# USB-IRIS-W1_POWER_COMM.net
KiCad netlist of a schematic drawn in Altium Designer
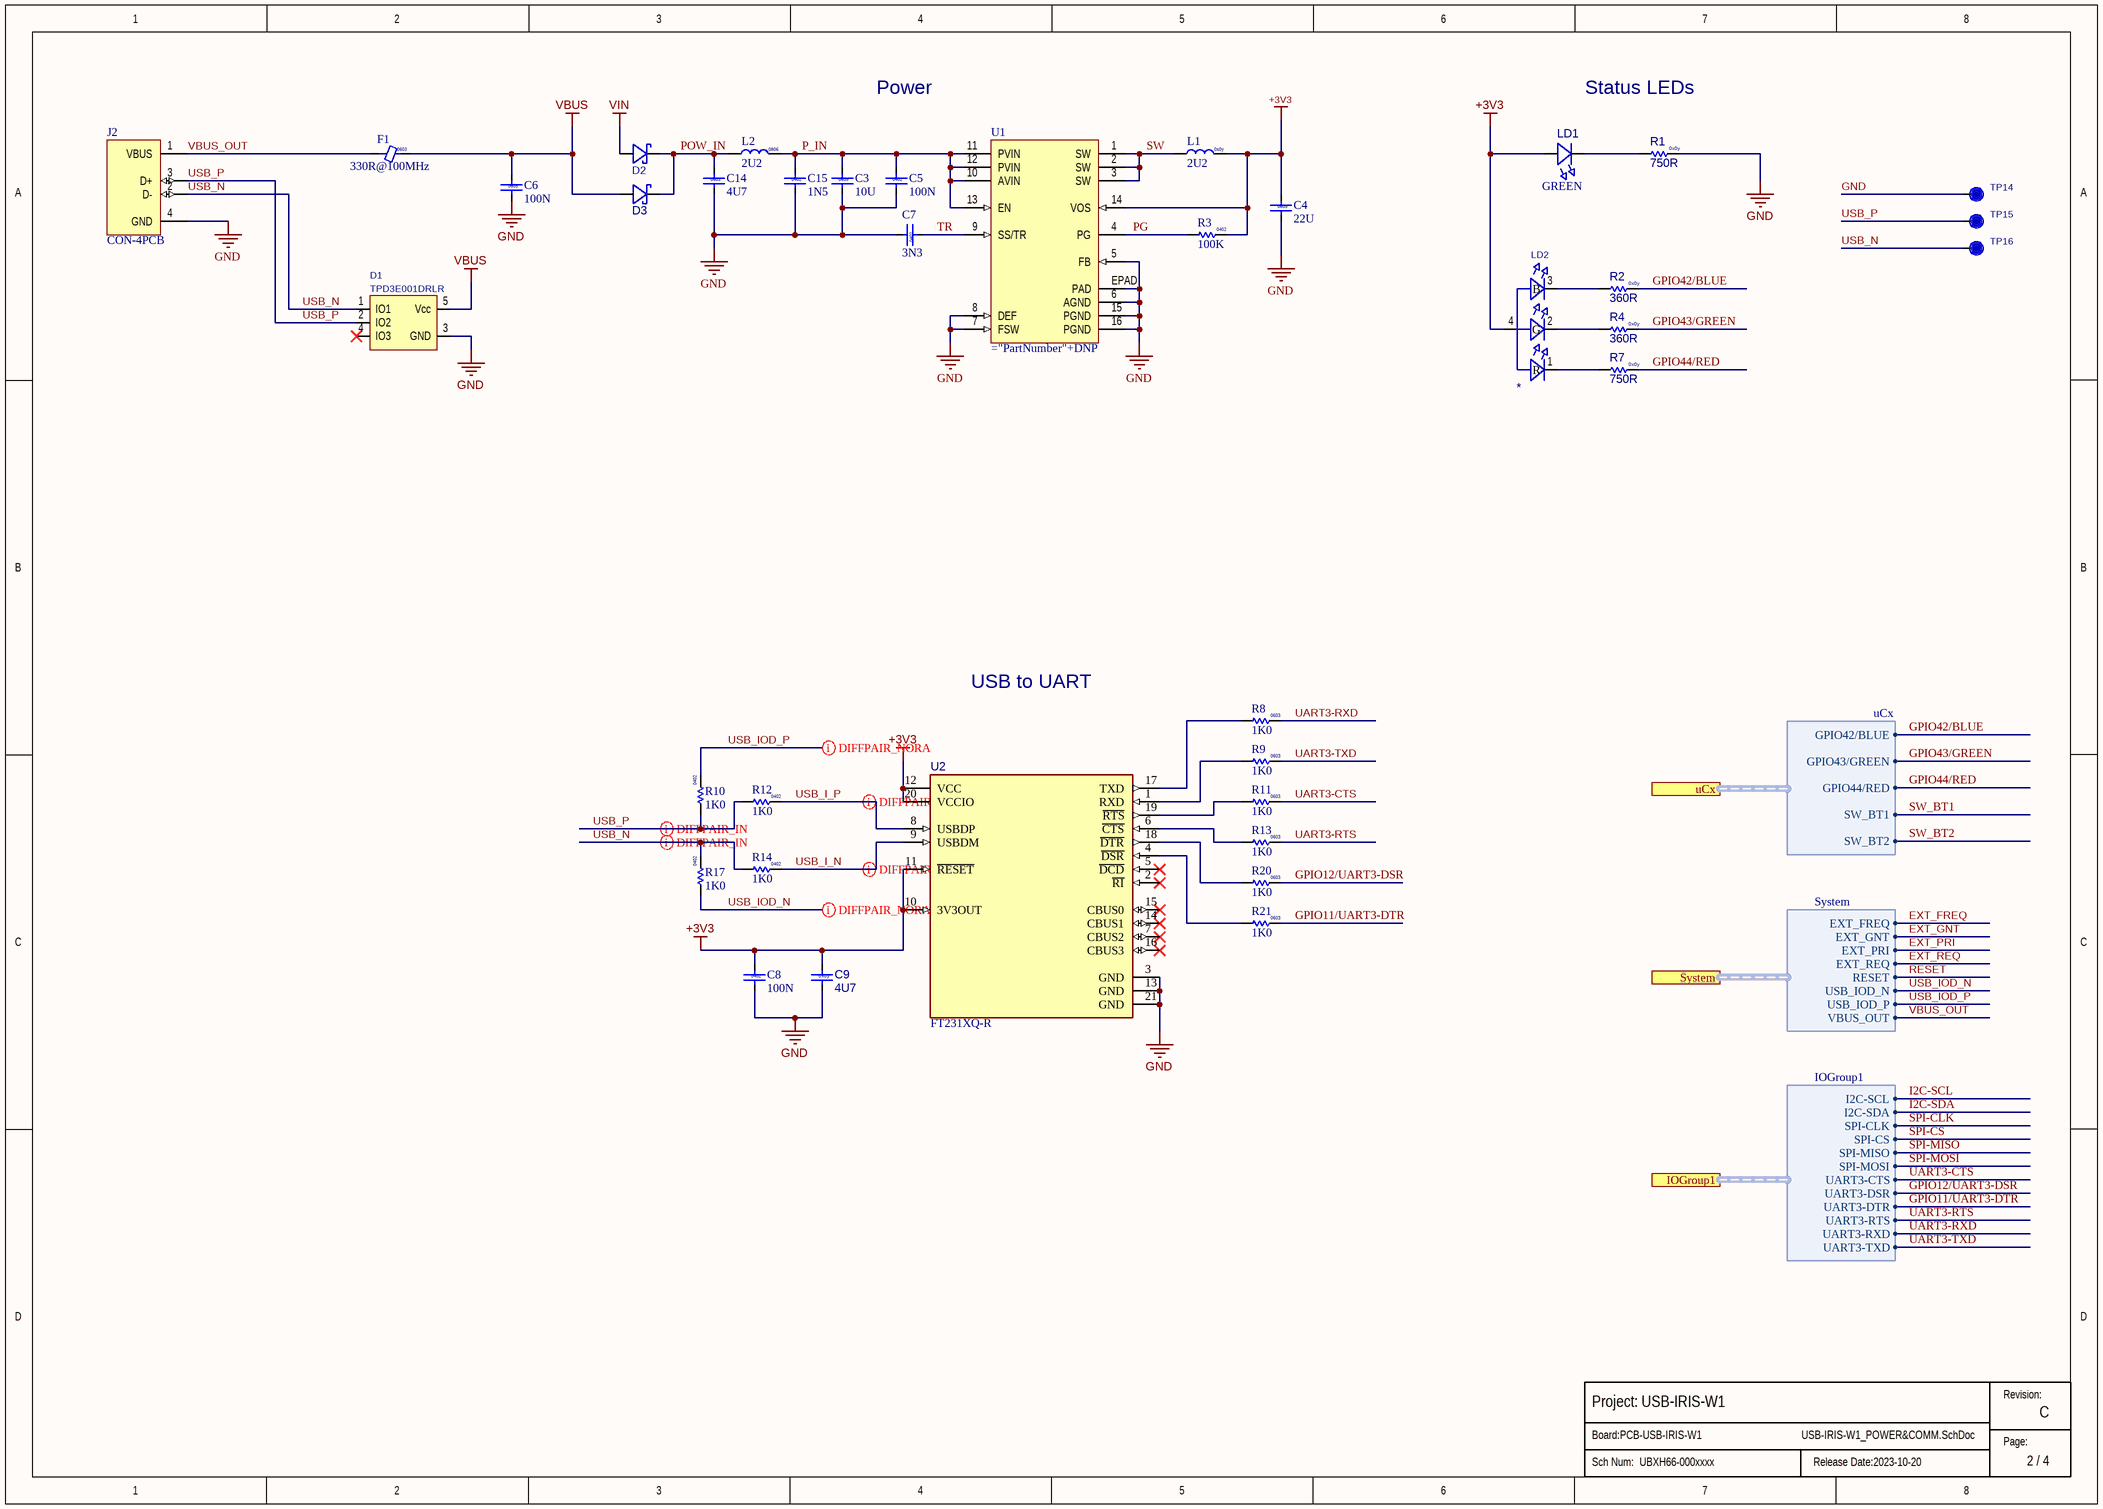
[diagram p0: USB-IRIS-W1_POWER&COMM.SchDoc]

(export (version "E")
  (design (tool "Eeschema 10.0.6"))
  (components
    (comp (ref "C3")
      (value "10U")
      (footprint "Cap 0805 HD")
      (description "CAP CER X5R 0805 10U 10% 25V")
      (fields
        (field (name "SIZE") "0805")
        (field (name "PART NUMBER") "UBXH01-0000261")
        (field (name "TOLERANCE") "10%")
        (field (name "EDITOR") "erian.bezhani")
        (field (name "RELEASED BY") "alex.claville")
      )
      (libsource (lib "UBX_Parts_DB_Lib") (part "Cap Chip"))
    )
    (comp (ref "C4")
      (value "22U")
      (footprint "Cap 0805 HD")
      (description "CAP CER X5R 0805 22U 20% 25V")
      (fields
        (field (name "SIZE") "0805")
        (field (name "PART NUMBER") "UBXH01-0000414")
        (field (name "TOLERANCE") "20%")
        (field (name "EDITOR") "jaakko.jussila")
      )
      (libsource (lib "UBX_Parts_DB_Lib") (part "Cap Chip"))
    )
    (comp (ref "C5")
      (value "100N")
      (footprint "Cap 0402 HD")
      (description "CAP CER X5R 0402 100N 10% 10V")
      (fields
        (field (name "SIZE") "0402")
        (field (name "PART NUMBER") "UBXH01-2021002")
        (field (name "TOLERANCE") "10%")
        (field (name "EDITOR") "roland.rust")
        (field (name "RELEASED BY") "roland.rust")
      )
      (libsource (lib "UBX_Parts_DB_Lib") (part "Cap Chip"))
    )
    (comp (ref "C6")
      (value "100N")
      (footprint "CAP_0603_1750Lx950Wx850H_600x1000Pad_900G_FLX")
      (description "CAP CER X7R 0603 100N 10% 50V")
      (fields
        (field (name "SIZE") "0603")
        (field (name "PART NUMBER") "UBXH01-2022001")
        (field (name "TOLERANCE") "10%")
        (field (name "EDITOR") "andreas.thiel")
        (field (name "RELEASED BY") "johann.furrer")
      )
      (libsource (lib "UBX_Parts_DB_Lib") (part "Cap Chip"))
    )
    (comp (ref "C7")
      (value "3N3")
      (footprint "CAP 0402")
      (description "CAP CER X7R 0402 3N3 10% 16V")
      (fields
        (field (name "SIZE") "0402")
        (field (name "PART NUMBER") "UBXH01-0023019")
        (field (name "TOLERANCE") "10%")
        (field (name "EDITOR") "dario.antonaz")
        (field (name "RELEASED BY") "pierpaolo.arban")
      )
      (libsource (lib "UBX_Parts_DB_Lib") (part "Cap Chip"))
    )
    (comp (ref "C8")
      (value "100N")
      (footprint "Cap 0402 HD")
      (description "CAP CER X5R 0402 100N 10% 10V")
      (fields
        (field (name "SIZE") "0402")
        (field (name "PART NUMBER") "UBXH01-2021002")
        (field (name "TOLERANCE") "10%")
        (field (name "EDITOR") "roland.rust")
        (field (name "RELEASED BY") "roland.rust")
      )
      (libsource (lib "UBX_Parts_DB_Lib") (part "Cap Chip"))
    )
    (comp (ref "C9")
      (value "4U7")
      (footprint "Cap 0402 HD")
      (description "CAP CER X5R 0402")
      (fields
        (field (name "SIZE") "0x0y")
        (field (name "PART NUMBER") "UBXH01-0000243")
        (field (name "TOLERANCE") "20%")
        (field (name "EDITOR") "dario.antonaz")
        (field (name "RELEASED BY") "pasquale.scorca")
      )
      (libsource (lib "UBX_Parts_DB_Lib") (part "Cap Chip"))
    )
    (comp (ref "C14")
      (value "4U7")
      (footprint "CAP_0603_1800Lx1000Wx1000H_600x1000Pad_900G_FLX")
      (description "CAP CER X5R 0603 4U7 20% 10V")
      (fields
        (field (name "SIZE") "0603")
        (field (name "PART NUMBER") "UBXH01-0000247")
        (field (name "TOLERANCE") "20%")
        (field (name "EDITOR") "dario.antonaz")
        (field (name "RELEASED BY") "martin.grasse")
      )
      (libsource (lib "UBX_Parts_DB_Lib") (part "Cap Chip"))
    )
    (comp (ref "C15")
      (value "1N5")
      (footprint "CAP 0402")
      (description "CAP CER X7R 0402 1N5 10% 50V")
      (fields
        (field (name "SIZE") "0402")
        (field (name "PART NUMBER") "UBXH01-0000211")
        (field (name "TOLERANCE") "10%")
        (field (name "EDITOR") "domenico.volpe")
        (field (name "RELEASED BY") "massimo.vlacci")
      )
      (libsource (lib "UBX_Parts_DB_Lib") (part "Cap Chip"))
    )
    (comp (ref "D1")
      (value "110-00018")
      (footprint "SOT-553")
      (description "LOW-CAPACITANCE 3-CHANNEL ESD-PROTECTION ARRAY")
      (fields
        (field (name "MANUFACTURER P/N") "TPD3E001DRLR")
        (field (name "MANUFACTURER") "Texas Instruments")
        (field (name "VOLTAGE") "5V")
      )
      (libsource (lib "Arena_Parts_DB_Lib") (part "TPD3E001"))
    )
    (comp (ref "D2")
      (value "110-00005")
      (footprint "SOD-123F_U")
      (description "Diode, Schottky, 20V 1A SOD-123F, 340mV Vf @ 1A\nMBR120VLSFT3G")
      (fields (field (name "VOLTAGE") "20V"))
      (libsource (lib "Arena_Parts_DB_Lib") (part "Diode_Schottky"))
    )
    (comp (ref "D3")
      (value "110-00005")
      (footprint "SOD-123F_U")
      (description "Diode, Schottky, 20V 1A SOD-123F, 340mV Vf @ 1A\nMBR120VLSFT3G")
      (fields (field (name "VOLTAGE") "20V"))
      (libsource (lib "Arena_Parts_DB_Lib") (part "Diode_Schottky"))
    )
    (comp (ref "F1")
      (value "330R@100MHz")
      (footprint "IND 0603 HD:IND 0603 HD")
      (description "FERRITE BEAD MURATA BLM18KG 0603 330R@100MHz")
      (fields (field (name "MANUFACTURER") "Murata Electronics") (field (name "SIZE") "0603"))
      (libsource (lib "Schlib1") (part "FB sm"))
    )
    (comp (ref "J2")
      (value "CON-4PCB")
      (footprint "USB-A-PCB")
      (description "CONN USB PLUG A TYPE PCB FOOTPRINT")
      (fields (field (name "PART NUMBER") "UBXH04-0000711") (field (name "EDITOR") "aneeb.sohail"))
      (libsource (lib "UBX_Parts_DB_Lib") (part "CON-4PCB"))
    )
    (comp (ref "L1")
      (value "2U2")
      (footprint "Ind_4mmx4mm")
      (description "SHIELDED POWER INDUCTOR XFL4020 2U2 20% 3.1A")
      (fields
        (field (name "SIZE") "0x0y")
        (field (name "PART NUMBER") "UBXH09-0000176")
        (field (name "TOLERANCE") "20%")
        (field (name "EDITOR") "roland.rust")
        (field (name "RELEASED BY") "olof.viklund")
      )
      (libsource (lib "UBX_Parts_DB_Lib") (part "Ind sm"))
    )
    (comp (ref "L2")
      (value "2U2")
      (footprint "IND 0806")
      (description "IND MURATA LQM2MP 0806 2U2 30% 1.2A")
      (fields
        (field (name "SIZE") "0806")
        (field (name "PART NUMBER") "UBXH09-0000025")
        (field (name "TOLERANCE") "30%")
        (field (name "EDITOR") "martin.pilik")
        (field (name "RELEASED BY") "fabrice.bret-dibat")
      )
      (libsource (lib "UBX_Parts_DB_Lib") (part "Ind sm"))
    )
    (comp (ref "LD1")
      (value "GREEN")
      (footprint "LED-0603")
      (description "LED CHIP 0603 LOW CURRENT OSRAM 0.002A")
      (fields
        (field (name "PART NUMBER") "UBXH11-0000018")
        (field (name "MANUFACTURER") "Osram")
        (field (name "EDITOR") "johann.furrer")
        (field (name "RELEASED BY") "martin.grasse")
      )
      (libsource (lib "UBX_Parts_DB_Lib") (part "LED_BASE"))
    )
    (comp (ref "LD2")
      (value "115-00026")
      (footprint "LED_1616")
      (description "LED RGB SMT 0606")
      (fields (field (name "COLOR") "*") (field (name "VOLTAGE") "None"))
      (libsource (lib "Arena_Parts_DB_Lib") (part "LED_RGB_CA_4"))
    )
    (comp (ref "R1")
      (value "750R")
      (footprint "RES 0402 HD")
      (description "RES THICK FILM CHIP 0402")
      (fields
        (field (name "SIZE") "0x0y")
        (field (name "PART NUMBER") "UBXH18-0008046")
        (field (name "TOLERANCE") "5%")
        (field (name "EDITOR") "jaka.bevk")
        (field (name "RELEASED BY") "erian.bezhani")
      )
      (libsource (lib "UBX_Parts_DB_Lib") (part "Res sm"))
    )
    (comp (ref "R2")
      (value "360R")
      (footprint "RES 0402 HD")
      (description "RES THICK FILM CHIP 0402")
      (fields
        (field (name "SIZE") "0x0y")
        (field (name "PART NUMBER") "UBXH18-0000216")
        (field (name "TOLERANCE") "1%")
        (field (name "EDITOR") "michael.hein")
        (field (name "RELEASED BY") "vasyl.dykyy")
      )
      (libsource (lib "UBX_Parts_DB_Lib") (part "Res sm"))
    )
    (comp (ref "R3")
      (value "100K")
      (footprint "RES 0402 HD")
      (description "RES THICK FILM CHIP 0402 100K 1% 63mW")
      (fields
        (field (name "SIZE") "0402")
        (field (name "PART NUMBER") "UBXH18-0000005")
        (field (name "TOLERANCE") "1%")
        (field (name "EDITOR") "dario.antonaz")
        (field (name "RELEASED BY") "sandro.sestan")
      )
      (libsource (lib "UBX_Parts_DB_Lib") (part "Res sm"))
    )
    (comp (ref "R4")
      (value "360R")
      (footprint "RES 0402 HD")
      (description "RES THICK FILM CHIP 0402")
      (fields
        (field (name "SIZE") "0x0y")
        (field (name "PART NUMBER") "UBXH18-0000216")
        (field (name "TOLERANCE") "1%")
        (field (name "EDITOR") "michael.hein")
        (field (name "RELEASED BY") "vasyl.dykyy")
      )
      (libsource (lib "UBX_Parts_DB_Lib") (part "Res sm"))
    )
    (comp (ref "R7")
      (value "750R")
      (footprint "RES 0402 HD")
      (description "RES THICK FILM CHIP 0402")
      (fields
        (field (name "SIZE") "0x0y")
        (field (name "PART NUMBER") "UBXH18-0008046")
        (field (name "TOLERANCE") "5%")
        (field (name "EDITOR") "jaka.bevk")
        (field (name "RELEASED BY") "erian.bezhani")
      )
      (libsource (lib "UBX_Parts_DB_Lib") (part "Res sm"))
    )
    (comp (ref "R8")
      (value "1K0")
      (footprint "RES 0603 HD")
      (description "RES THICK FILM CHIP 0603 1K0 5% 100mW")
      (fields
        (field (name "SIZE") "0603")
        (field (name "PART NUMBER") "UBXH18-0007073")
        (field (name "TOLERANCE") "5%")
        (field (name "EDITOR") "roland.rust")
        (field (name "RELEASED BY") "roland.rust")
      )
      (libsource (lib "UBX_Parts_DB_Lib") (part "Res sm"))
    )
    (comp (ref "R9")
      (value "1K0")
      (footprint "RES 0603 HD")
      (description "RES THICK FILM CHIP 0603 1K0 5% 100mW")
      (fields
        (field (name "SIZE") "0603")
        (field (name "PART NUMBER") "UBXH18-0007073")
        (field (name "TOLERANCE") "5%")
        (field (name "EDITOR") "roland.rust")
        (field (name "RELEASED BY") "roland.rust")
      )
      (libsource (lib "UBX_Parts_DB_Lib") (part "Res sm"))
    )
    (comp (ref "R10")
      (value "1K0")
      (footprint "RES 0402 HD")
      (description "RES THICK FILM CHIP 0402 1K0 5% 100mW")
      (fields
        (field (name "SIZE") "0402")
        (field (name "PART NUMBER") "UBXH18-0008049")
        (field (name "TOLERANCE") "5%")
        (field (name "EDITOR") "roland.rust")
        (field (name "RELEASED BY") "roland.rust")
      )
      (libsource (lib "UBX_Parts_DB_Lib") (part "Res sm"))
    )
    (comp (ref "R11")
      (value "1K0")
      (footprint "RES 0603 HD")
      (description "RES THICK FILM CHIP 0603 1K0 5% 100mW")
      (fields
        (field (name "SIZE") "0603")
        (field (name "PART NUMBER") "UBXH18-0007073")
        (field (name "TOLERANCE") "5%")
        (field (name "EDITOR") "roland.rust")
        (field (name "RELEASED BY") "roland.rust")
      )
      (libsource (lib "UBX_Parts_DB_Lib") (part "Res sm"))
    )
    (comp (ref "R12")
      (value "1K0")
      (footprint "RES 0402 HD")
      (description "RES THICK FILM CHIP 0402 1K0 5% 100mW")
      (fields
        (field (name "SIZE") "0402")
        (field (name "PART NUMBER") "UBXH18-0008049")
        (field (name "TOLERANCE") "5%")
        (field (name "EDITOR") "roland.rust")
        (field (name "RELEASED BY") "roland.rust")
      )
      (libsource (lib "UBX_Parts_DB_Lib") (part "Res sm"))
    )
    (comp (ref "R13")
      (value "1K0")
      (footprint "RES 0603 HD")
      (description "RES THICK FILM CHIP 0603 1K0 5% 100mW")
      (fields
        (field (name "SIZE") "0603")
        (field (name "PART NUMBER") "UBXH18-0007073")
        (field (name "TOLERANCE") "5%")
        (field (name "EDITOR") "roland.rust")
        (field (name "RELEASED BY") "roland.rust")
      )
      (libsource (lib "UBX_Parts_DB_Lib") (part "Res sm"))
    )
    (comp (ref "R14")
      (value "1K0")
      (footprint "RES 0402 HD")
      (description "RES THICK FILM CHIP 0402 1K0 5% 100mW")
      (fields
        (field (name "SIZE") "0402")
        (field (name "PART NUMBER") "UBXH18-0008049")
        (field (name "TOLERANCE") "5%")
        (field (name "EDITOR") "roland.rust")
        (field (name "RELEASED BY") "roland.rust")
      )
      (libsource (lib "UBX_Parts_DB_Lib") (part "Res sm"))
    )
    (comp (ref "R17")
      (value "1K0")
      (footprint "RES 0402 HD")
      (description "RES THICK FILM CHIP 0402 1K0 5% 100mW")
      (fields
        (field (name "SIZE") "0402")
        (field (name "PART NUMBER") "UBXH18-0008049")
        (field (name "TOLERANCE") "5%")
        (field (name "EDITOR") "roland.rust")
        (field (name "RELEASED BY") "roland.rust")
      )
      (libsource (lib "UBX_Parts_DB_Lib") (part "Res sm"))
    )
    (comp (ref "R20")
      (value "1K0")
      (footprint "RES 0603 HD")
      (description "RES THICK FILM CHIP 0603 1K0 5% 100mW")
      (fields
        (field (name "SIZE") "0603")
        (field (name "PART NUMBER") "UBXH18-0007073")
        (field (name "TOLERANCE") "5%")
        (field (name "EDITOR") "roland.rust")
        (field (name "RELEASED BY") "roland.rust")
      )
      (libsource (lib "UBX_Parts_DB_Lib") (part "Res sm"))
    )
    (comp (ref "R21")
      (value "1K0")
      (footprint "RES 0603 HD")
      (description "RES THICK FILM CHIP 0603 1K0 5% 100mW")
      (fields
        (field (name "SIZE") "0603")
        (field (name "PART NUMBER") "UBXH18-0007073")
        (field (name "TOLERANCE") "5%")
        (field (name "EDITOR") "roland.rust")
        (field (name "RELEASED BY") "roland.rust")
      )
      (libsource (lib "UBX_Parts_DB_Lib") (part "Res sm"))
    )
    (comp (ref "TP14")
      (value "TP")
      (footprint "TP10R")
      (description "Testpoint, Round 1.0mm Dia")
      (fields
        (field (name "PART NUMBER") "TP10R")
        (field (name "ADDED BY") "Jeremy D")
        (field (name "CHECKED BY") "Paul B")
      )
      (libsource (lib "LEGACY_Rigado_AltiumLib") (part "TP_R"))
    )
    (comp (ref "TP15")
      (value "TP")
      (footprint "TP10R")
      (description "Testpoint, Round 1.0mm Dia")
      (fields
        (field (name "PART NUMBER") "TP10R")
        (field (name "ADDED BY") "Jeremy D")
        (field (name "CHECKED BY") "Paul B")
      )
      (libsource (lib "LEGACY_Rigado_AltiumLib") (part "TP_R"))
    )
    (comp (ref "TP16")
      (value "TP")
      (footprint "TP10R")
      (description "Testpoint, Round 1.0mm Dia")
      (fields
        (field (name "PART NUMBER") "TP10R")
        (field (name "ADDED BY") "Jeremy D")
        (field (name "CHECKED BY") "Paul B")
      )
      (libsource (lib "LEGACY_Rigado_AltiumLib") (part "TP_R"))
    )
    (comp (ref "U1")
      (value "TPS62132RGTR")
      (footprint "QFN0.5P3x3-16Pin_W-Pad")
      (description "STEP DOWN DC-DC CONVERTER 3-17V 3A TPS62132 3V3")
      (fields
        (field (name "MANUFACTURER") "Texas Instruments")
        (field (name "PART NUMBER") "UBXH12-0000160")
        (field (name "EDITOR") "andre.pick")
        (field (name "RELEASED BY") "alvaro.nussbaum")
      )
      (libsource (lib "Schlib1") (part "UBXH12-0000160"))
    )
    (comp (ref "U2")
      (value "FT231XQ-R")
      (footprint "QFN_5x5_FT231XQ")
      (description "FTDI USB TO SERIAL FULL UART INTERFACE QFN20")
      (fields
        (field (name "PART NUMBER") "UBXH10-0000054")
        (field (name "MANUFACTURER") "FTDI Future Technology Devices International")
        (field (name "EDITOR") "adam.johansson")
      )
      (libsource (lib "UBX_Parts_DB_Lib") (part "FT231XQ-R"))
    )
  )
  (nets
    (net (code "4") (name "+3V3") (class "Default")
      (node (ref "C4") (pin "1") (pinfunction "1_1") (pintype "passive"))
      (node (ref "C8") (pin "1") (pinfunction "1_1") (pintype "passive"))
      (node (ref "C9") (pin "1") (pinfunction "1_1") (pintype "passive"))
      (node (ref "L1") (pin "2") (pinfunction "2_2") (pintype "passive"))
      (node (ref "LD1") (pin "2") (pinfunction "A_2") (pintype "passive"))
      (node (ref "LD2") (pin "4") (pinfunction "A_4") (pintype "passive"))
      (node (ref "R3") (pin "2") (pinfunction "2_2") (pintype "passive"))
      (node (ref "U1") (pin "14") (pinfunction "VOS_14") (pintype "input"))
      (node (ref "U2") (pin "10") (pinfunction "3V3OUT_10") (pintype "input"))
      (node (ref "U2") (pin "11") (pinfunction "~{RESET}_11") (pintype "input"))
      (node (ref "U2") (pin "12") (pinfunction "VCC_12") (pintype "power_in"))
      (node (ref "U2") (pin "20") (pinfunction "VCCIO_20") (pintype "power_in"))
    )
    (net (code "9") (name "/GPIO11{slash}UART3-DTR") (class "Default")
      (node (ref "R21") (pin "2") (pinfunction "2_2") (pintype "passive"))
    )
    (net (code "10") (name "/GPIO12{slash}UART3-DSR") (class "Default")
      (node (ref "R20") (pin "2") (pinfunction "2_2") (pintype "passive"))
    )
    (net (code "11") (name "/GPIO42{slash}BLUE") (class "Default")
      (node (ref "R2") (pin "2") (pinfunction "2_2") (pintype "passive"))
    )
    (net (code "12") (name "/GPIO43{slash}GREEN") (class "Default")
      (node (ref "R4") (pin "2") (pinfunction "2_2") (pintype "passive"))
    )
    (net (code "13") (name "/GPIO44{slash}RED") (class "Default")
      (node (ref "R7") (pin "2") (pinfunction "2_2") (pintype "passive"))
    )
    (net (code "16") (name "/PG") (class "Default")
      (node (ref "R3") (pin "1") (pinfunction "1_1") (pintype "passive"))
      (node (ref "U1") (pin "4") (pinfunction "PG_4") (pintype "tri_state"))
    )
    (net (code "17") (name "/POW_IN") (class "Default")
      (node (ref "C14") (pin "1") (pinfunction "1_1") (pintype "passive"))
      (node (ref "D2") (pin "C") (pinfunction "Cathode_C") (pintype "passive"))
      (node (ref "D3") (pin "C") (pinfunction "Cathode_C") (pintype "passive"))
      (node (ref "L2") (pin "1") (pinfunction "1_1") (pintype "passive"))
    )
    (net (code "18") (name "/P_IN") (class "Default")
      (node (ref "C15") (pin "1") (pinfunction "1_1") (pintype "passive"))
      (node (ref "C3") (pin "1") (pinfunction "1_1") (pintype "passive"))
      (node (ref "C5") (pin "1") (pinfunction "1_1") (pintype "passive"))
      (node (ref "L2") (pin "2") (pinfunction "2_2") (pintype "passive"))
      (node (ref "U1") (pin "10") (pinfunction "AVIN_10") (pintype "power_in"))
      (node (ref "U1") (pin "11") (pinfunction "PVIN_11") (pintype "power_in"))
      (node (ref "U1") (pin "12") (pinfunction "PVIN_12") (pintype "power_in"))
      (node (ref "U1") (pin "13") (pinfunction "EN_13") (pintype "input"))
    )
    (net (code "24") (name "/SW") (class "Default")
      (node (ref "L1") (pin "1") (pinfunction "1_1") (pintype "passive"))
      (node (ref "U1") (pin "1") (pinfunction "SW_1") (pintype "power_in"))
      (node (ref "U1") (pin "2") (pinfunction "SW_2") (pintype "power_in"))
      (node (ref "U1") (pin "3") (pinfunction "SW_3") (pintype "power_in"))
    )
    (net (code "27") (name "/TR") (class "Default")
      (node (ref "C7") (pin "1") (pinfunction "1_1") (pintype "passive"))
      (node (ref "U1") (pin "9") (pinfunction "SS/TR_9") (pintype "input"))
    )
    (net (code "28") (name "/UART3-CTS") (class "Default")
      (node (ref "R11") (pin "2") (pinfunction "2_2") (pintype "passive"))
    )
    (net (code "29") (name "/UART3-RTS") (class "Default")
      (node (ref "R13") (pin "2") (pinfunction "2_2") (pintype "passive"))
    )
    (net (code "30") (name "/UART3-RXD") (class "Default")
      (node (ref "R8") (pin "2") (pinfunction "2_2") (pintype "passive"))
    )
    (net (code "31") (name "/UART3-TXD") (class "Default")
      (node (ref "R9") (pin "2") (pinfunction "2_2") (pintype "passive"))
    )
    (net (code "32") (name "/USB_IOD_N") (class "Default")
      (node (ref "R17") (pin "1") (pinfunction "1_1") (pintype "passive"))
    )
    (net (code "33") (name "/USB_IOD_P") (class "Default")
      (node (ref "R10") (pin "2") (pinfunction "2_2") (pintype "passive"))
    )
    (net (code "34") (name "/USB_I_N") (class "Default")
      (node (ref "R14") (pin "2") (pinfunction "2_2") (pintype "passive"))
      (node (ref "U2") (pin "9") (pinfunction "USBDM_9") (pintype "input"))
    )
    (net (code "35") (name "/USB_I_P") (class "Default")
      (node (ref "R12") (pin "2") (pinfunction "2_2") (pintype "passive"))
      (node (ref "U2") (pin "8") (pinfunction "USBDP_8") (pintype "input"))
    )
    (net (code "36") (name "/USB_N") (class "Default")
      (node (ref "D1") (pin "1") (pinfunction "IO1_1") (pintype "passive"))
      (node (ref "J2") (pin "2") (pinfunction "D-_2") (pintype "bidirectional"))
      (node (ref "R14") (pin "1") (pinfunction "1_1") (pintype "passive"))
      (node (ref "R17") (pin "2") (pinfunction "2_2") (pintype "passive"))
      (node (ref "TP16") (pin "1") (pintype "passive"))
    )
    (net (code "37") (name "/USB_P") (class "Default")
      (node (ref "D1") (pin "2") (pinfunction "IO2_2") (pintype "passive"))
      (node (ref "J2") (pin "3") (pinfunction "D+_3") (pintype "bidirectional"))
      (node (ref "R10") (pin "1") (pinfunction "1_1") (pintype "passive"))
      (node (ref "R12") (pin "1") (pinfunction "1_1") (pintype "passive"))
      (node (ref "TP15") (pin "1") (pintype "passive"))
    )
    (net (code "38") (name "/VBUS_OUT") (class "Default")
      (node (ref "F1") (pin "1") (pinfunction "1_1") (pintype "passive"))
      (node (ref "J2") (pin "1") (pinfunction "VBUS_1") (pintype "power_in"))
    )
    (net (code "42") (name "GND") (class "Default")
      (node (ref "C14") (pin "2") (pinfunction "2_2") (pintype "passive"))
      (node (ref "C15") (pin "2") (pinfunction "2_2") (pintype "passive"))
      (node (ref "C3") (pin "2") (pinfunction "2_2") (pintype "passive"))
      (node (ref "C4") (pin "2") (pinfunction "2_2") (pintype "passive"))
      (node (ref "C5") (pin "2") (pinfunction "2_2") (pintype "passive"))
      (node (ref "C6") (pin "2") (pinfunction "2_2") (pintype "passive"))
      (node (ref "C7") (pin "2") (pinfunction "2_2") (pintype "passive"))
      (node (ref "C8") (pin "2") (pinfunction "2_2") (pintype "passive"))
      (node (ref "C9") (pin "2") (pinfunction "2_2") (pintype "passive"))
      (node (ref "D1") (pin "3") (pinfunction "GND_3") (pintype "power_in"))
      (node (ref "J2") (pin "4") (pinfunction "GND_4") (pintype "power_in"))
      (node (ref "R1") (pin "2") (pinfunction "2_2") (pintype "passive"))
      (node (ref "TP14") (pin "1") (pintype "passive"))
      (node (ref "U1") (pin "15") (pinfunction "PGND_15") (pintype "power_in"))
      (node (ref "U1") (pin "16") (pinfunction "PGND_16") (pintype "power_in"))
      (node (ref "U1") (pin "5") (pinfunction "FB_5") (pintype "input"))
      (node (ref "U1") (pin "6") (pinfunction "AGND_6") (pintype "power_in"))
      (node (ref "U1") (pin "7") (pinfunction "FSW_7") (pintype "input"))
      (node (ref "U1") (pin "8") (pinfunction "DEF_8") (pintype "input"))
      (node (ref "U1") (pin "EPAD") (pinfunction "PAD_EPAD") (pintype "power_in"))
      (node (ref "U2") (pin "13") (pinfunction "GND_13") (pintype "power_in"))
      (node (ref "U2") (pin "21") (pinfunction "GND_21") (pintype "power_in"))
      (node (ref "U2") (pin "3") (pinfunction "GND_3") (pintype "power_in"))
    )
    (net (code "43") (name "Net-(LD1-C)") (class "Default")
      (node (ref "LD1") (pin "1") (pinfunction "C_1") (pintype "passive"))
      (node (ref "R1") (pin "1") (pinfunction "1_1") (pintype "passive"))
    )
    (net (code "44") (name "Net-(LD2-B)") (class "Default")
      (node (ref "LD2") (pin "3") (pinfunction "B_3") (pintype "passive"))
      (node (ref "R2") (pin "1") (pinfunction "1_1") (pintype "passive"))
    )
    (net (code "45") (name "Net-(LD2-G)") (class "Default")
      (node (ref "LD2") (pin "2") (pinfunction "G_2") (pintype "passive"))
      (node (ref "R4") (pin "1") (pinfunction "1_1") (pintype "passive"))
    )
    (net (code "46") (name "Net-(LD2-R)") (class "Default")
      (node (ref "LD2") (pin "1") (pinfunction "R_1") (pintype "passive"))
      (node (ref "R7") (pin "1") (pinfunction "1_1") (pintype "passive"))
    )
    (net (code "47") (name "Net-(U2-RXD)") (class "Default")
      (node (ref "R9") (pin "1") (pinfunction "1_1") (pintype "passive"))
      (node (ref "U2") (pin "1") (pinfunction "RXD_1") (pintype "input"))
    )
    (net (code "48") (name "Net-(U2-TXD)") (class "Default")
      (node (ref "R8") (pin "1") (pinfunction "1_1") (pintype "passive"))
      (node (ref "U2") (pin "17") (pinfunction "TXD_17") (pintype "output"))
    )
    (net (code "49") (name "Net-(U2-~{CTS})") (class "Default")
      (node (ref "R13") (pin "1") (pinfunction "1_1") (pintype "passive"))
      (node (ref "U2") (pin "6") (pinfunction "~{CTS}_6") (pintype "input"))
    )
    (net (code "50") (name "Net-(U2-~{DSR})") (class "Default")
      (node (ref "R21") (pin "1") (pinfunction "1_1") (pintype "passive"))
      (node (ref "U2") (pin "4") (pinfunction "~{DSR}_4") (pintype "input"))
    )
    (net (code "51") (name "Net-(U2-~{DTR})") (class "Default")
      (node (ref "R20") (pin "1") (pinfunction "1_1") (pintype "passive"))
      (node (ref "U2") (pin "18") (pinfunction "~{DTR}_18") (pintype "output"))
    )
    (net (code "52") (name "Net-(U2-~{RTS})") (class "Default")
      (node (ref "R11") (pin "1") (pinfunction "1_1") (pintype "passive"))
      (node (ref "U2") (pin "19") (pinfunction "~{RTS}_19") (pintype "output"))
    )
    (net (code "53") (name "VBUS") (class "Default")
      (node (ref "C6") (pin "1") (pinfunction "1_1") (pintype "passive"))
      (node (ref "D1") (pin "5") (pinfunction "Vcc_5") (pintype "power_in"))
      (node (ref "D3") (pin "A") (pinfunction "Anode_A") (pintype "passive"))
      (node (ref "F1") (pin "2") (pinfunction "2_2") (pintype "passive"))
    )
    (net (code "54") (name "VIN") (class "Default")
      (node (ref "D2") (pin "A") (pinfunction "Anode_A") (pintype "passive"))
    )
    (net (code "55") (name "unconnected-(D1-IO3-Pad4)") (class "Default")
      (node (ref "D1") (pin "4") (pinfunction "IO3_4") (pintype "passive+no_connect"))
    )
    (net (code "56") (name "unconnected-(U2-CBUS0-Pad15)") (class "Default")
      (node (ref "U2") (pin "15") (pinfunction "CBUS0_15") (pintype "bidirectional+no_connect"))
    )
    (net (code "57") (name "unconnected-(U2-CBUS1-Pad14)") (class "Default")
      (node (ref "U2") (pin "14") (pinfunction "CBUS1_14") (pintype "bidirectional+no_connect"))
    )
    (net (code "58") (name "unconnected-(U2-CBUS2-Pad7)") (class "Default")
      (node (ref "U2") (pin "7") (pinfunction "CBUS2_7") (pintype "bidirectional+no_connect"))
    )
    (net (code "59") (name "unconnected-(U2-CBUS3-Pad16)") (class "Default")
      (node (ref "U2") (pin "16") (pinfunction "CBUS3_16") (pintype "bidirectional+no_connect"))
    )
    (net (code "60") (name "unconnected-(U2-~{DCD}-Pad5)") (class "Default")
      (node (ref "U2") (pin "5") (pinfunction "~{DCD}_5") (pintype "input+no_connect"))
    )
    (net (code "61") (name "unconnected-(U2-~{RI}-Pad2)") (class "Default")
      (node (ref "U2") (pin "2") (pinfunction "~{RI}_2") (pintype "input+no_connect"))
    )
  )
)
